# power_rev_2.net
KiCad netlist of a schematic drawn in EAGLE
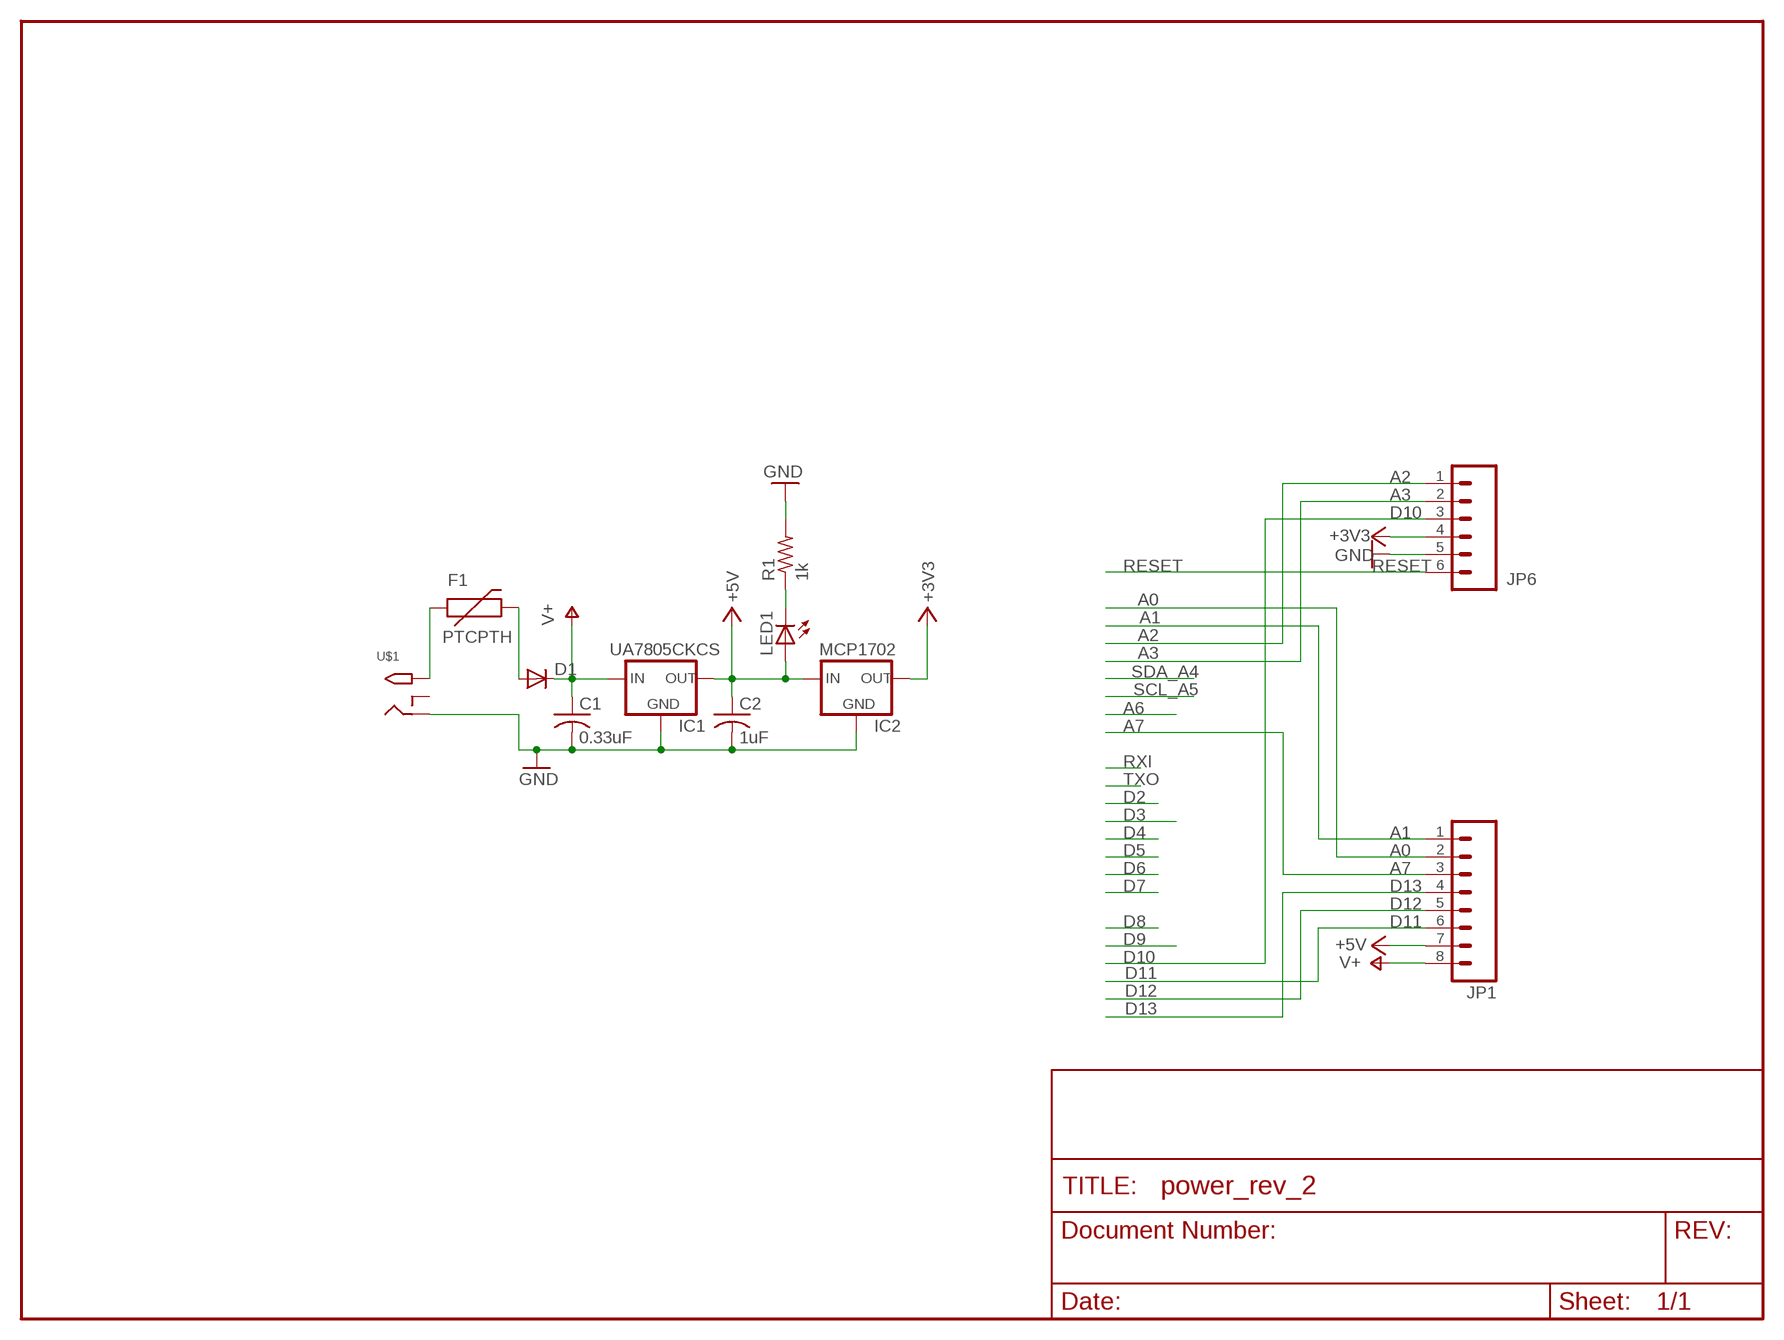
[diagram p0: schematic, sheet 1]

(export (version "E")
  (design (tool "Eeschema 10.0.6"))
  (components
    (comp (ref "C1")
      (value "0.33uF")
      (footprint "eagle-import:C025-024X044")
      (libsource (lib "eagle-import") (part "C-US025-024X044"))
    )
    (comp (ref "C2")
      (value "1uF")
      (footprint "eagle-import:C025-024X044")
      (libsource (lib "eagle-import") (part "C-US025-024X044"))
    )
    (comp (ref "D1")
      (value "DIODE1N4148")
      (footprint "eagle-import:DIODE-1N4148")
      (libsource (lib "eagle-import") (part "DIODE1N4148"))
    )
    (comp (ref "F1")
      (value "PTCPTH")
      (footprint "eagle-import:PTC")
      (libsource (lib "eagle-import") (part "PTCPTH"))
    )
    (comp (ref "IC1")
      (value "UA7805CKCS")
      (footprint "eagle-import:TO-220-ALT")
      (libsource (lib "eagle-import") (part "V_REG_78XX-TO-220"))
    )
    (comp (ref "IC2")
      (value "MCP1702")
      (footprint "eagle-import:TO92-INLINE")
      (libsource (lib "eagle-import") (part "MCP1700INLINE"))
    )
    (comp (ref "JP1")
      (value "M081X08")
      (footprint "eagle-import:1X08")
      (libsource (lib "eagle-import") (part "M081X08"))
    )
    (comp (ref "JP6")
      (value "M06SIP")
      (footprint "eagle-import:1X06")
      (libsource (lib "eagle-import") (part "M06SIP"))
    )
    (comp (ref "LED1")
      (value "LED3MM")
      (footprint "eagle-import:LED3MM")
      (libsource (lib "eagle-import") (part "LED3MM"))
    )
    (comp (ref "R1")
      (value "1k")
      (footprint "eagle-import:0204_5")
      (libsource (lib "eagle-import") (part "R-US_0204/5"))
    )
    (comp (ref "U$1")
      (value "2.1MMJACKTHM")
      (footprint "eagle-import:PJ-102A")
      (libsource (lib "eagle-import") (part "2.1MMJACKTHM"))
    )
  )
  (nets
    (net (code "1") (name "+3V3") (class "Default")
      (node (ref "IC2") (pin "3") (pinfunction "OUT_3") (pintype "passive"))
      (node (ref "JP6") (pin "4") (pinfunction "4_4") (pintype "passive"))
    )
    (net (code "2") (name "+5V") (class "Default")
      (node (ref "C2") (pin "1") (pinfunction "1_1") (pintype "passive"))
      (node (ref "IC1") (pin "OUT") (pinfunction "OUT_OUT") (pintype "output"))
      (node (ref "IC2") (pin "2") (pinfunction "IN_2") (pintype "input"))
      (node (ref "JP1") (pin "7") (pinfunction "7_7") (pintype "passive"))
      (node (ref "LED1") (pin "A") (pinfunction "A_A") (pintype "passive"))
    )
    (net (code "3") (name "/A0") (class "Default")
      (node (ref "JP1") (pin "2") (pinfunction "2_2") (pintype "passive"))
    )
    (net (code "4") (name "/A1") (class "Default")
      (node (ref "JP1") (pin "1") (pinfunction "1_1") (pintype "passive"))
    )
    (net (code "5") (name "/A2") (class "Default")
      (node (ref "JP6") (pin "1") (pinfunction "1_1") (pintype "passive"))
    )
    (net (code "6") (name "/A3") (class "Default")
      (node (ref "JP6") (pin "2") (pinfunction "2_2") (pintype "passive"))
    )
    (net (code "8") (name "/A7") (class "Default")
      (node (ref "JP1") (pin "3") (pinfunction "3_3") (pintype "passive"))
    )
    (net (code "17") (name "/D10") (class "Default")
      (node (ref "JP6") (pin "3") (pinfunction "3_3") (pintype "passive"))
    )
    (net (code "18") (name "/D11") (class "Default")
      (node (ref "JP1") (pin "6") (pinfunction "6_6") (pintype "passive"))
    )
    (net (code "19") (name "/D12") (class "Default")
      (node (ref "JP1") (pin "5") (pinfunction "5_5") (pintype "passive"))
    )
    (net (code "20") (name "/D13") (class "Default")
      (node (ref "JP1") (pin "4") (pinfunction "4_4") (pintype "passive"))
    )
    (net (code "21") (name "/RESET") (class "Default")
      (node (ref "JP6") (pin "6") (pinfunction "6_6") (pintype "passive"))
    )
    (net (code "26") (name "GND") (class "Default")
      (node (ref "C1") (pin "2") (pinfunction "2_2") (pintype "passive"))
      (node (ref "C2") (pin "2") (pinfunction "2_2") (pintype "passive"))
      (node (ref "IC1") (pin "GND") (pinfunction "GND_GND") (pintype "input"))
      (node (ref "IC2") (pin "1") (pinfunction "GND_1") (pintype "input"))
      (node (ref "JP6") (pin "5") (pinfunction "5_5") (pintype "passive"))
      (node (ref "R1") (pin "2") (pinfunction "2_2") (pintype "passive"))
      (node (ref "U$1") (pin "RING") (pinfunction "RING_RING") (pintype "bidirectional"))
    )
    (net (code "27") (name "Net-(F1-1)") (class "Default")
      (node (ref "F1") (pin "P$1") (pinfunction "1_P$1") (pintype "bidirectional"))
      (node (ref "U$1") (pin "TIP") (pinfunction "TIP_TIP") (pintype "bidirectional"))
    )
    (net (code "28") (name "Net-(F1-2)") (class "Default")
      (node (ref "D1") (pin "A") (pinfunction "A_A") (pintype "passive"))
      (node (ref "F1") (pin "P$2") (pinfunction "2_P$2") (pintype "bidirectional"))
    )
    (net (code "29") (name "Net-(LED1-C)") (class "Default")
      (node (ref "LED1") (pin "K") (pinfunction "C_K") (pintype "passive"))
      (node (ref "R1") (pin "1") (pinfunction "1_1") (pintype "passive"))
    )
    (net (code "30") (name "V+") (class "Default")
      (node (ref "C1") (pin "1") (pinfunction "1_1") (pintype "passive"))
      (node (ref "D1") (pin "C") (pinfunction "C_C") (pintype "passive"))
      (node (ref "IC1") (pin "IN") (pinfunction "IN_IN") (pintype "input"))
      (node (ref "JP1") (pin "8") (pinfunction "8_8") (pintype "passive"))
    )
    (net (code "31") (name "unconnected-(U$1-PadRING_SW)") (class "Default")
      (node (ref "U$1") (pin "RING_SW") (pinfunction "RING_SW_RING_SW") (pintype "bidirectional"))
    )
  )
)
